# Scheme.net
KiCad netlist of a schematic drawn in Altium Designer
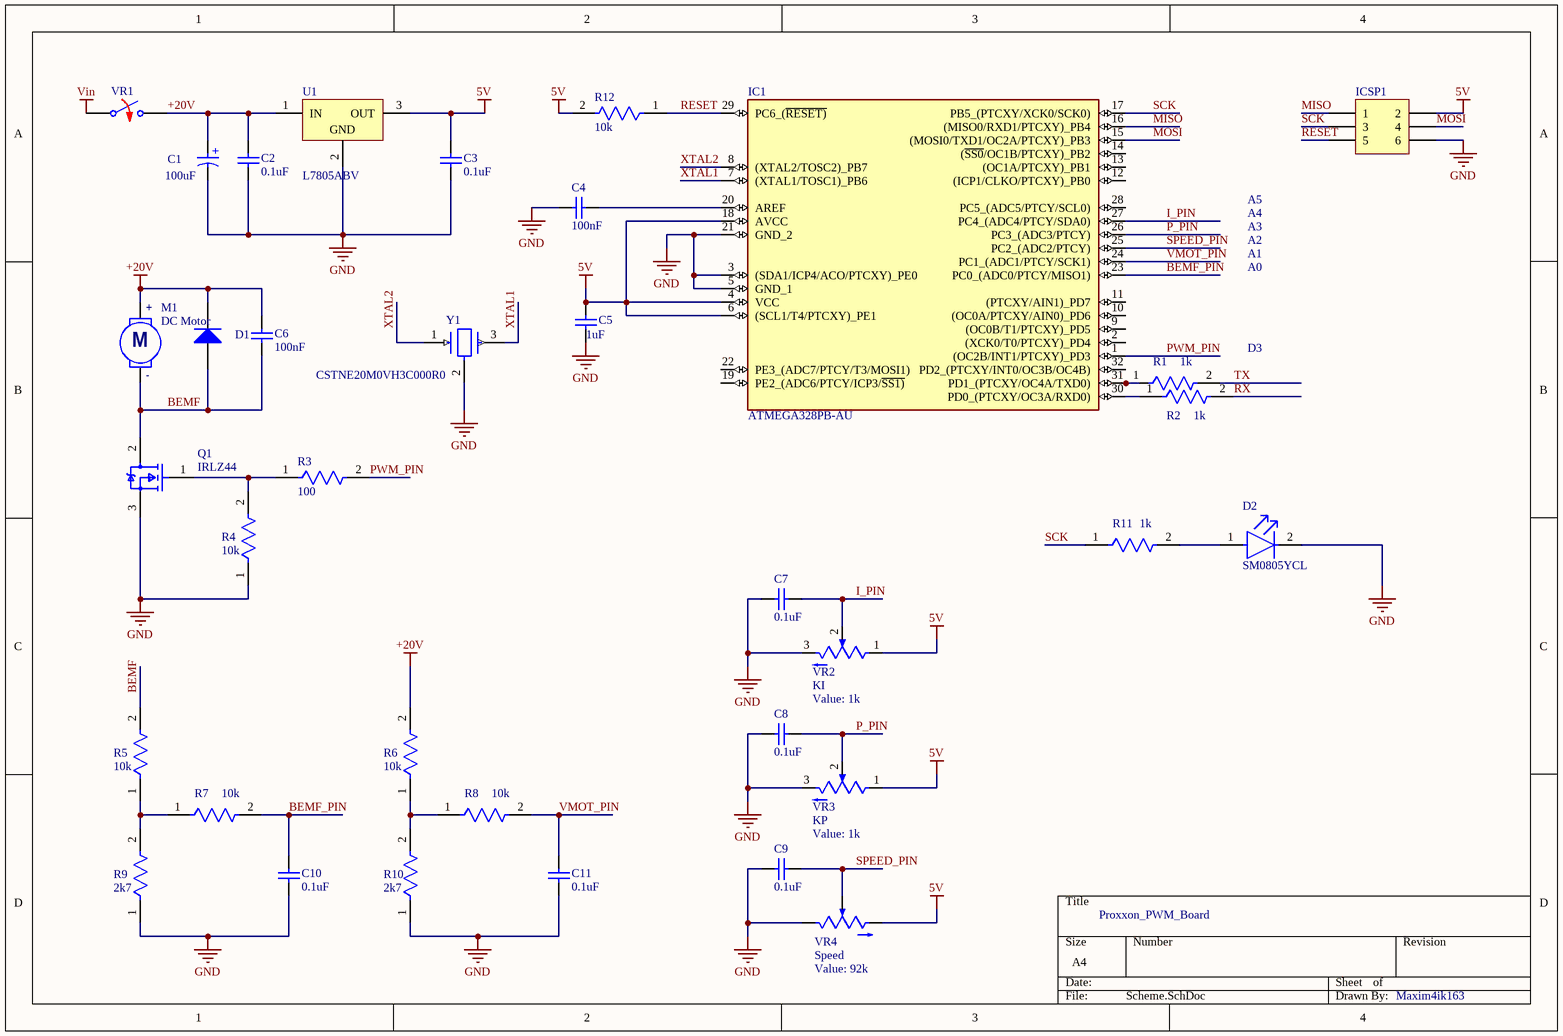
[diagram p0: Scheme.SchDoc]

(export (version "E")
  (design (tool "Eeschema 10.0.6"))
  (components
    (comp (ref "C1")
      (value "100uF")
      (footprint "WCAP-ATLL_D8H11.5")
      (description "Aluminium Electrolytic Capacitor-Leaded Rohs Compliant: Yes")
      (fields (field (name "TOLERANCE") "20%"))
      (libsource (lib "Altium Content Vault") (part "Capacitor_Polarized"))
    )
    (comp (ref "C2")
      (value "0.1uF")
      (footprint "CAPC1608X92X38ML15T08")
      (fields (field (name "MANUFACTURER") "Vitramon") (field (name "PART NUMBER") "VJ0603Y102KXXAC"))
      (libsource (lib "Altium Content Vault") (part "CAP"))
    )
    (comp (ref "C3")
      (value "0.1uF")
      (footprint "CAPC1608X92X38ML15T08")
      (fields (field (name "MANUFACTURER") "Vitramon") (field (name "PART NUMBER") "VJ0603Y102KXXAC"))
      (libsource (lib "Altium Content Vault") (part "CAP"))
    )
    (comp (ref "C4")
      (value "100nF")
      (footprint "CAPC1608X92X38ML15T08")
      (fields (field (name "MANUFACTURER") "Vitramon") (field (name "PART NUMBER") "VJ0603Y102KXXAC"))
      (libsource (lib "Altium Content Vault") (part "CAP"))
    )
    (comp (ref "C5")
      (value "1uF")
      (footprint "CAPC1608X92X38ML15T08")
      (fields (field (name "MANUFACTURER") "Vitramon") (field (name "PART NUMBER") "VJ0603Y102KXXAC"))
      (libsource (lib "Altium Content Vault") (part "CAP"))
    )
    (comp (ref "C6")
      (value "100nF")
      (footprint "CAPC1608X92X38ML15T08")
      (fields (field (name "MANUFACTURER") "Vitramon") (field (name "PART NUMBER") "VJ0603Y102KXXAC"))
      (libsource (lib "Altium Content Vault") (part "CAP"))
    )
    (comp (ref "C7")
      (value "0.1uF")
      (footprint "CAPC1608X92X38ML15T08")
      (fields (field (name "MANUFACTURER") "Vitramon") (field (name "PART NUMBER") "VJ0603Y102KXXAC"))
      (libsource (lib "Altium Content Vault") (part "CAP"))
    )
    (comp (ref "C8")
      (value "0.1uF")
      (footprint "CAPC1608X92X38ML15T08")
      (fields (field (name "MANUFACTURER") "Vitramon") (field (name "PART NUMBER") "VJ0603Y102KXXAC"))
      (libsource (lib "Altium Content Vault") (part "CAP"))
    )
    (comp (ref "C9")
      (value "0.1uF")
      (footprint "CAPC1608X92X38ML15T08")
      (fields (field (name "MANUFACTURER") "Vitramon") (field (name "PART NUMBER") "VJ0603Y102KXXAC"))
      (libsource (lib "Altium Content Vault") (part "CAP"))
    )
    (comp (ref "C10")
      (value "0.1uF")
      (footprint "CAPC1608X92X38ML15T08")
      (fields (field (name "MANUFACTURER") "Vitramon") (field (name "PART NUMBER") "VJ0603Y102KXXAC"))
      (libsource (lib "Altium Content Vault") (part "CAP"))
    )
    (comp (ref "C11")
      (value "0.1uF")
      (footprint "CAPC1608X92X38ML15T08")
      (fields (field (name "MANUFACTURER") "Vitramon") (field (name "PART NUMBER") "VJ0603Y102KXXAC"))
      (libsource (lib "Altium Content Vault") (part "CAP"))
    )
    (comp (ref "D1")
      (value "Diode 1N4006")
      (footprint "DIO10.46-5.3x2.8")
      (description "1 Amp General Purpose Rectifier")
      (fields (field (name "PUBLISHER") "Altium Limited"))
      (libsource (lib "Miscellaneous Devices") (part "Diode 1N4006"))
    )
    (comp (ref "D2")
      (value "SM0805YCL")
      (footprint "FP-SM0805YCL-MFG")
      (description "LED YELLOW CLEAR 0805 SMD")
      (libsource (lib "Altium Content Vault") (part "ab1c01a81903e929fc6c44469aada92"))
    )
    (comp (ref "IC1")
      (value "ATMEGA328PB-AU")
      (footprint "QFP80P900X900X120-32N")
      (fields (field (name "MF") "Microchip Technology") (field (name "MP") "ATMEGA328PBAU"))
      (libsource (lib "ATMEGA328PB-AU") (part "ATMEGA328PB-AU"))
    )
    (comp (ref "ICSP1")
      (value "~")
      (footprint "PBS3x2")
      (description "Header, 3-Pin, Dual row")
      (fields (field (name "PUBLISHER") "Altium Limited"))
      (libsource (lib "Proxxon_PWM") (part "Header 3X2A"))
    )
    (comp (ref "M1")
      (value "DC Motor")
      (footprint "placeholder")
      (libsource (lib "Proxxon_PWM") (part "DC Motor"))
    )
    (comp (ref "Q1")
      (value "IRLZ44")
      (footprint "FP-PG-TO220-3-MFG")
      (description "MOSFET N-CH 55V 47A TO220AB")
      (libsource (lib "Altium Content Vault") (part "b09f7f152735e370c1ea22a33fa83d6"))
    )
    (comp (ref "R1")
      (value "1k")
      (footprint "FP-MCT0603-MFG")
      (description "RES SMD 100 OHM 1% 1/8W 0603")
      (fields (field (name "TOLERANCE") "0.1%"))
      (libsource (lib "Altium Content Vault") (part "1029c3af85768c4190bb7ad29bc67b5"))
    )
    (comp (ref "R2")
      (value "1k")
      (footprint "FP-MCT0603-MFG")
      (description "RES SMD 100 OHM 1% 1/8W 0603")
      (fields (field (name "TOLERANCE") "0.1%"))
      (libsource (lib "Altium Content Vault") (part "1029c3af85768c4190bb7ad29bc67b5"))
    )
    (comp (ref "R3")
      (value "100")
      (footprint "FP-MCT0603-MFG")
      (description "RES SMD 100 OHM 1% 1/8W 0603")
      (fields (field (name "TOLERANCE") "0.1%"))
      (libsource (lib "Altium Content Vault") (part "1029c3af85768c4190bb7ad29bc67b5"))
    )
    (comp (ref "R4")
      (value "10k")
      (footprint "FP-MCT0603-MFG")
      (description "RES SMD 100 OHM 1% 1/8W 0603")
      (fields (field (name "TOLERANCE") "0.1%"))
      (libsource (lib "Altium Content Vault") (part "1029c3af85768c4190bb7ad29bc67b5"))
    )
    (comp (ref "R5")
      (value "10k")
      (footprint "FP-MCT0603-MFG")
      (description "RES SMD 100 OHM 1% 1/8W 0603")
      (fields (field (name "TOLERANCE") "0.1%"))
      (libsource (lib "Altium Content Vault") (part "1029c3af85768c4190bb7ad29bc67b5"))
    )
    (comp (ref "R6")
      (value "10k")
      (footprint "FP-MCT0603-MFG")
      (description "RES SMD 100 OHM 1% 1/8W 0603")
      (fields (field (name "TOLERANCE") "0.1%"))
      (libsource (lib "Altium Content Vault") (part "1029c3af85768c4190bb7ad29bc67b5"))
    )
    (comp (ref "R7")
      (value "10k")
      (footprint "FP-MCT0603-MFG")
      (description "RES SMD 100 OHM 1% 1/8W 0603")
      (fields (field (name "TOLERANCE") "0.1%"))
      (libsource (lib "Altium Content Vault") (part "1029c3af85768c4190bb7ad29bc67b5"))
    )
    (comp (ref "R8")
      (value "10k")
      (footprint "FP-MCT0603-MFG")
      (description "RES SMD 100 OHM 1% 1/8W 0603")
      (fields (field (name "TOLERANCE") "0.1%"))
      (libsource (lib "Altium Content Vault") (part "1029c3af85768c4190bb7ad29bc67b5"))
    )
    (comp (ref "R9")
      (value "2k7")
      (footprint "FP-MCT0603-MFG")
      (description "RES SMD 100 OHM 1% 1/8W 0603")
      (fields (field (name "TOLERANCE") "0.1%"))
      (libsource (lib "Altium Content Vault") (part "1029c3af85768c4190bb7ad29bc67b5"))
    )
    (comp (ref "R10")
      (value "2k7")
      (footprint "FP-MCT0603-MFG")
      (description "RES SMD 100 OHM 1% 1/8W 0603")
      (fields (field (name "TOLERANCE") "0.1%"))
      (libsource (lib "Altium Content Vault") (part "1029c3af85768c4190bb7ad29bc67b5"))
    )
    (comp (ref "R11")
      (value "1k")
      (footprint "FP-MCT0603-MFG")
      (description "RES SMD 100 OHM 1% 1/8W 0603")
      (fields (field (name "TOLERANCE") "0.1%"))
      (libsource (lib "Altium Content Vault") (part "1029c3af85768c4190bb7ad29bc67b5"))
    )
    (comp (ref "R12")
      (value "10k")
      (footprint "FP-MCT0603-MFG")
      (description "RES SMD 100 OHM 1% 1/8W 0603")
      (fields (field (name "TOLERANCE") "0.1%"))
      (libsource (lib "Altium Content Vault") (part "1029c3af85768c4190bb7ad29bc67b5"))
    )
    (comp (ref "U1")
      (value "L7805ABV")
      (footprint "TO220")
      (description "Positive Voltage Regulator, 5V, 3-Pin TO-220")
      (libsource (lib "Altium Content Vault") (part "PM-REG-L4940-SIL3"))
    )
    (comp (ref "VR1")
      (value "Switch Normally Opened")
      (footprint "placeholder")
      (libsource (lib "Proxxon_PWM") (part "SW NO"))
    )
    (comp (ref "VR2")
      (value "KI")
      (footprint "TRIM_3362W-1-203LF")
      (description "1/4 Sq, Thru-Hole, TRIMMER, 20 Kilohms, Cermet, Single Turn ¦ Bourns 3362W-1-203LF")
      (fields
        (field (name "ALTIUM_VALUE") "1k")
        (field (name "MF") "Bourns")
        (field (name "MP") "3362W-1-203LF")
      )
      (libsource (lib "3362W-1-203LF") (part "3362W-1-203LF"))
    )
    (comp (ref "VR3")
      (value "KP")
      (footprint "TRIM_3362W-1-203LF")
      (description "1/4 Sq, Thru-Hole, TRIMMER, 20 Kilohms, Cermet, Single Turn ¦ Bourns 3362W-1-203LF")
      (fields
        (field (name "ALTIUM_VALUE") "1k")
        (field (name "MF") "Bourns")
        (field (name "MP") "3362W-1-203LF")
      )
      (libsource (lib "3362W-1-203LF") (part "3362W-1-203LF"))
    )
    (comp (ref "VR4")
      (value "Speed")
      (footprint "Res-var - COMPACT")
      (description "1/4 Sq, Thru-Hole, TRIMMER, 20 Kilohms, Cermet, Single Turn ¦ Bourns 3362W-1-203LF")
      (fields
        (field (name "MF") "Bourns")
        (field (name "MP") "3362W-1-203LF")
        (field (name "ALTIUM_VALUE") "92k")
      )
      (libsource (lib "Proxxon_PWM") (part "Res-var"))
    )
    (comp (ref "Y1")
      (value "CSTNE20M0VH3C000R0")
      (footprint "FP-CSTNE20M0VH3C000R0-MFG")
      (description "CERAMIC RES 20.0000MHZ 15PF SMD")
      (libsource (lib "Altium Content Vault") (part "7d37667f5012bb31280c8009ddd0b1c"))
    )
  )
  (nets
    (net (code "1") (name "+20V") (class "Default")
      (node (ref "C1") (pin "1") (pinfunction "P_1") (pintype "passive"))
      (node (ref "C2") (pin "2") (pinfunction "2_2") (pintype "passive"))
      (node (ref "C6") (pin "2") (pinfunction "2_2") (pintype "passive"))
      (node (ref "D1") (pin "2") (pinfunction "K_2") (pintype "passive"))
      (node (ref "M1") (pin "1") (pinfunction "+_1") (pintype "passive"))
      (node (ref "R6") (pin "2") (pinfunction "2_2") (pintype "passive"))
      (node (ref "U1") (pin "1") (pinfunction "IN_1") (pintype "power_in"))
      (node (ref "VR1") (pin "2") (pinfunction "2_2") (pintype "passive"))
    )
    (net (code "2") (name "/BEMF") (class "Default")
      (node (ref "C6") (pin "1") (pinfunction "1_1") (pintype "passive"))
      (node (ref "D1") (pin "1") (pinfunction "A_1") (pintype "passive"))
      (node (ref "M1") (pin "2") (pinfunction "-_2") (pintype "passive"))
      (node (ref "Q1") (pin "2") (pinfunction "D_2") (pintype "passive"))
      (node (ref "R5") (pin "2") (pinfunction "2_2") (pintype "passive"))
    )
    (net (code "3") (name "/BEMF_PIN") (class "Default")
      (node (ref "C10") (pin "2") (pinfunction "2_2") (pintype "passive"))
      (node (ref "IC1") (pin "23") (pinfunction "PC0_(ADC0/PTCY/MISO1)_23") (pintype "bidirectional"))
      (node (ref "R7") (pin "2") (pinfunction "2_2") (pintype "passive"))
    )
    (net (code "4") (name "/I_PIN") (class "Default")
      (node (ref "C7") (pin "2") (pinfunction "2_2") (pintype "passive"))
      (node (ref "IC1") (pin "27") (pinfunction "PC4_(ADC4/PTCY/SDA0)_27") (pintype "bidirectional"))
      (node (ref "VR2") (pin "2") (pinfunction "WIPER_2") (pintype "passive"))
    )
    (net (code "5") (name "/MISO") (class "Default")
      (node (ref "IC1") (pin "16") (pinfunction "(MISO0/RXD1/PTCXY)_PB4_16") (pintype "bidirectional"))
      (node (ref "ICSP1") (pin "1") (pinfunction "1_1") (pintype "passive"))
    )
    (net (code "6") (name "/MOSI") (class "Default")
      (node (ref "IC1") (pin "15") (pinfunction "(MOSI0/TXD1/OC2A/PTCXY)_PB3_15") (pintype "bidirectional"))
      (node (ref "ICSP1") (pin "4") (pinfunction "4_4") (pintype "passive"))
    )
    (net (code "7") (name "/PWM_PIN") (class "Default")
      (node (ref "IC1") (pin "1") (pinfunction "(OC2B/INT1/PTCXY)_PD3_1") (pintype "bidirectional"))
      (node (ref "R3") (pin "2") (pinfunction "2_2") (pintype "passive"))
    )
    (net (code "8") (name "/P_PIN") (class "Default")
      (node (ref "C8") (pin "2") (pinfunction "2_2") (pintype "passive"))
      (node (ref "IC1") (pin "26") (pinfunction "PC3_(ADC3/PTCY)_26") (pintype "bidirectional"))
      (node (ref "VR3") (pin "2") (pinfunction "WIPER_2") (pintype "passive"))
    )
    (net (code "9") (name "/RESET") (class "Default")
      (node (ref "IC1") (pin "29") (pinfunction "PC6_(~{RESET)}_29") (pintype "bidirectional"))
      (node (ref "ICSP1") (pin "5") (pinfunction "5_5") (pintype "passive"))
      (node (ref "R12") (pin "1") (pinfunction "1_1") (pintype "passive"))
    )
    (net (code "10") (name "/RX") (class "Default")
      (node (ref "R2") (pin "2") (pinfunction "2_2") (pintype "passive"))
    )
    (net (code "11") (name "/SCK") (class "Default")
      (node (ref "IC1") (pin "17") (pinfunction "PB5_(PTCXY/XCK0/SCK0)_17") (pintype "bidirectional"))
      (node (ref "ICSP1") (pin "3") (pinfunction "3_3") (pintype "passive"))
      (node (ref "R11") (pin "1") (pinfunction "1_1") (pintype "passive"))
    )
    (net (code "12") (name "/SPEED_PIN") (class "Default")
      (node (ref "C9") (pin "2") (pinfunction "2_2") (pintype "passive"))
      (node (ref "IC1") (pin "25") (pinfunction "PC2_(ADC2/PTCY)_25") (pintype "bidirectional"))
      (node (ref "VR4") (pin "2") (pinfunction "WIPER_2") (pintype "passive"))
    )
    (net (code "13") (name "/TX") (class "Default")
      (node (ref "R1") (pin "2") (pinfunction "2_2") (pintype "passive"))
    )
    (net (code "14") (name "/VMOT_PIN") (class "Default")
      (node (ref "C11") (pin "2") (pinfunction "2_2") (pintype "passive"))
      (node (ref "IC1") (pin "24") (pinfunction "PC1_(ADC1/PTCY/SCK1)_24") (pintype "bidirectional"))
      (node (ref "R8") (pin "2") (pinfunction "2_2") (pintype "passive"))
    )
    (net (code "15") (name "/XTAL1") (class "Default")
      (node (ref "IC1") (pin "7") (pinfunction "(XTAL1/TOSC1)_PB6_7") (pintype "bidirectional"))
      (node (ref "Y1") (pin "3") (pinfunction "Output_3") (pintype "output"))
    )
    (net (code "16") (name "/XTAL2") (class "Default")
      (node (ref "IC1") (pin "8") (pinfunction "(XTAL2/TOSC2)_PB7_8") (pintype "bidirectional"))
      (node (ref "Y1") (pin "1") (pinfunction "Input_1") (pintype "input"))
    )
    (net (code "17") (name "5V") (class "Default")
      (node (ref "C3") (pin "2") (pinfunction "2_2") (pintype "passive"))
      (node (ref "C5") (pin "2") (pinfunction "2_2") (pintype "passive"))
      (node (ref "IC1") (pin "18") (pinfunction "AVCC_18") (pintype "bidirectional"))
      (node (ref "IC1") (pin "4") (pinfunction "VCC_4") (pintype "bidirectional"))
      (node (ref "IC1") (pin "6") (pinfunction "(SCL1/T4/PTCXY)_PE1_6") (pintype "bidirectional"))
      (node (ref "ICSP1") (pin "2") (pinfunction "2_2") (pintype "passive"))
      (node (ref "R12") (pin "2") (pinfunction "2_2") (pintype "passive"))
      (node (ref "U1") (pin "3") (pinfunction "OUT_3") (pintype "power_in"))
      (node (ref "VR2") (pin "1") (pinfunction "CCW_1") (pintype "passive"))
      (node (ref "VR3") (pin "1") (pinfunction "CCW_1") (pintype "passive"))
      (node (ref "VR4") (pin "3") (pinfunction "CW_3") (pintype "passive"))
    )
    (net (code "18") (name "GND") (class "Default")
      (node (ref "C1") (pin "2") (pinfunction "N_2") (pintype "passive"))
      (node (ref "C10") (pin "1") (pinfunction "1_1") (pintype "passive"))
      (node (ref "C11") (pin "1") (pinfunction "1_1") (pintype "passive"))
      (node (ref "C2") (pin "1") (pinfunction "1_1") (pintype "passive"))
      (node (ref "C3") (pin "1") (pinfunction "1_1") (pintype "passive"))
      (node (ref "C4") (pin "2") (pinfunction "2_2") (pintype "passive"))
      (node (ref "C5") (pin "1") (pinfunction "1_1") (pintype "passive"))
      (node (ref "C7") (pin "1") (pinfunction "1_1") (pintype "passive"))
      (node (ref "C8") (pin "1") (pinfunction "1_1") (pintype "passive"))
      (node (ref "C9") (pin "1") (pinfunction "1_1") (pintype "passive"))
      (node (ref "D2") (pin "2") (pinfunction "C_2") (pintype "passive"))
      (node (ref "IC1") (pin "21") (pinfunction "GND_2_21") (pintype "bidirectional"))
      (node (ref "IC1") (pin "3") (pinfunction "(SDA1/ICP4/ACO/PTCXY)_PE0_3") (pintype "bidirectional"))
      (node (ref "IC1") (pin "5") (pinfunction "GND_1_5") (pintype "bidirectional"))
      (node (ref "ICSP1") (pin "6") (pinfunction "6_6") (pintype "passive"))
      (node (ref "Q1") (pin "3") (pinfunction "S_3") (pintype "passive"))
      (node (ref "R10") (pin "1") (pinfunction "1_1") (pintype "passive"))
      (node (ref "R4") (pin "1") (pinfunction "1_1") (pintype "passive"))
      (node (ref "R9") (pin "1") (pinfunction "1_1") (pintype "passive"))
      (node (ref "U1") (pin "2") (pinfunction "GND_2") (pintype "power_in"))
      (node (ref "VR2") (pin "3") (pinfunction "CW_3") (pintype "passive"))
      (node (ref "VR3") (pin "3") (pinfunction "CW_3") (pintype "passive"))
      (node (ref "VR4") (pin "1") (pinfunction "CCW_1") (pintype "passive"))
      (node (ref "Y1") (pin "2") (pinfunction "GND_2") (pintype "power_in"))
    )
    (net (code "19") (name "Net-(D2-A)") (class "Default")
      (node (ref "D2") (pin "1") (pinfunction "A_1") (pintype "passive"))
      (node (ref "R11") (pin "2") (pinfunction "2_2") (pintype "passive"))
    )
    (net (code "20") (name "Net-(IC1-AREF)") (class "Default")
      (node (ref "C4") (pin "1") (pinfunction "1_1") (pintype "passive"))
      (node (ref "IC1") (pin "20") (pinfunction "AREF_20") (pintype "bidirectional"))
    )
    (net (code "21") (name "Net-(IC1-PD0_(PTCXY{slash}OC3A{slash}RXD0))") (class "Default")
      (node (ref "IC1") (pin "30") (pinfunction "PD0_(PTCXY/OC3A/RXD0)_30") (pintype "bidirectional"))
      (node (ref "R2") (pin "1") (pinfunction "1_1") (pintype "passive"))
    )
    (net (code "22") (name "Net-(IC1-PD1_(PTCXY{slash}OC4A{slash}TXD0))") (class "Default")
      (node (ref "IC1") (pin "31") (pinfunction "PD1_(PTCXY/OC4A/TXD0)_31") (pintype "bidirectional"))
      (node (ref "R1") (pin "1") (pinfunction "1_1") (pintype "passive"))
    )
    (net (code "23") (name "Net-(Q1-G)") (class "Default")
      (node (ref "Q1") (pin "1") (pinfunction "G_1") (pintype "passive"))
      (node (ref "R3") (pin "1") (pinfunction "1_1") (pintype "passive"))
      (node (ref "R4") (pin "2") (pinfunction "2_2") (pintype "passive"))
    )
    (net (code "24") (name "Net-(R5-Pad1)") (class "Default")
      (node (ref "R5") (pin "1") (pinfunction "1_1") (pintype "passive"))
      (node (ref "R7") (pin "1") (pinfunction "1_1") (pintype "passive"))
      (node (ref "R9") (pin "2") (pinfunction "2_2") (pintype "passive"))
    )
    (net (code "25") (name "Net-(R10-Pad2)") (class "Default")
      (node (ref "R10") (pin "2") (pinfunction "2_2") (pintype "passive"))
      (node (ref "R6") (pin "1") (pinfunction "1_1") (pintype "passive"))
      (node (ref "R8") (pin "1") (pinfunction "1_1") (pintype "passive"))
    )
    (net (code "26") (name "Vin") (class "Default")
      (node (ref "VR1") (pin "1") (pinfunction "1_1") (pintype "passive"))
    )
    (net (code "27") (name "unconnected-(IC1-(ICP1{slash}CLKO{slash}PTCXY)_PB0-Pad12)") (class "Default")
      (node (ref "IC1") (pin "12") (pinfunction "(ICP1/CLKO/PTCXY)_PB0_12") (pintype "bidirectional"))
    )
    (net (code "28") (name "unconnected-(IC1-(OC0A{slash}PTCXY{slash}AIN0)_PD6-Pad10)") (class "Default")
      (node (ref "IC1") (pin "10") (pinfunction "(OC0A/PTCXY/AIN0)_PD6_10") (pintype "bidirectional"))
    )
    (net (code "29") (name "unconnected-(IC1-(OC0B{slash}T1{slash}PTCXY)_PD5-Pad9)") (class "Default")
      (node (ref "IC1") (pin "9") (pinfunction "(OC0B/T1/PTCXY)_PD5_9") (pintype "bidirectional"))
    )
    (net (code "30") (name "unconnected-(IC1-(OC1A{slash}PTCXY)_PB1-Pad13)") (class "Default")
      (node (ref "IC1") (pin "13") (pinfunction "(OC1A/PTCXY)_PB1_13") (pintype "bidirectional"))
    )
    (net (code "31") (name "unconnected-(IC1-(PTCXY{slash}AIN1)_PD7-Pad11)") (class "Default")
      (node (ref "IC1") (pin "11") (pinfunction "(PTCXY/AIN1)_PD7_11") (pintype "bidirectional"))
    )
    (net (code "32") (name "unconnected-(IC1-(XCK0{slash}T0{slash}PTCXY)_PD4-Pad2)") (class "Default")
      (node (ref "IC1") (pin "2") (pinfunction "(XCK0/T0/PTCXY)_PD4_2") (pintype "bidirectional"))
    )
    (net (code "33") (name "unconnected-(IC1-(~{SS0}{slash}OC1B{slash}PTCXY)_PB2-Pad14)") (class "Default")
      (node (ref "IC1") (pin "14") (pinfunction "(~{SS0}/OC1B/PTCXY)_PB2_14") (pintype "bidirectional"))
    )
    (net (code "34") (name "unconnected-(IC1-PC5_(ADC5{slash}PTCY{slash}SCL0)-Pad28)") (class "Default")
      (node (ref "IC1") (pin "28") (pinfunction "PC5_(ADC5/PTCY/SCL0)_28") (pintype "bidirectional"))
    )
    (net (code "35") (name "unconnected-(IC1-PD2_(PTCXY{slash}INT0{slash}OC3B{slash}OC4B)-Pad32)") (class "Default")
      (node (ref "IC1") (pin "32") (pinfunction "PD2_(PTCXY/INT0/OC3B/OC4B)_32") (pintype "bidirectional"))
    )
    (net (code "36") (name "unconnected-(IC1-PE2_(ADC6{slash}PTCY{slash}ICP3{slash}~{SS1)}-Pad19)") (class "Default")
      (node (ref "IC1") (pin "19") (pinfunction "PE2_(ADC6/PTCY/ICP3/~{SS1)}_19") (pintype "bidirectional"))
    )
    (net (code "37") (name "unconnected-(IC1-PE3_(ADC7{slash}PTCY{slash}T3{slash}MOSI1)-Pad22)") (class "Default")
      (node (ref "IC1") (pin "22") (pinfunction "PE3_(ADC7/PTCY/T3/MOSI1)_22") (pintype "bidirectional"))
    )
  )
)
